# receiver.net
KiCad netlist of a schematic drawn in EAGLE
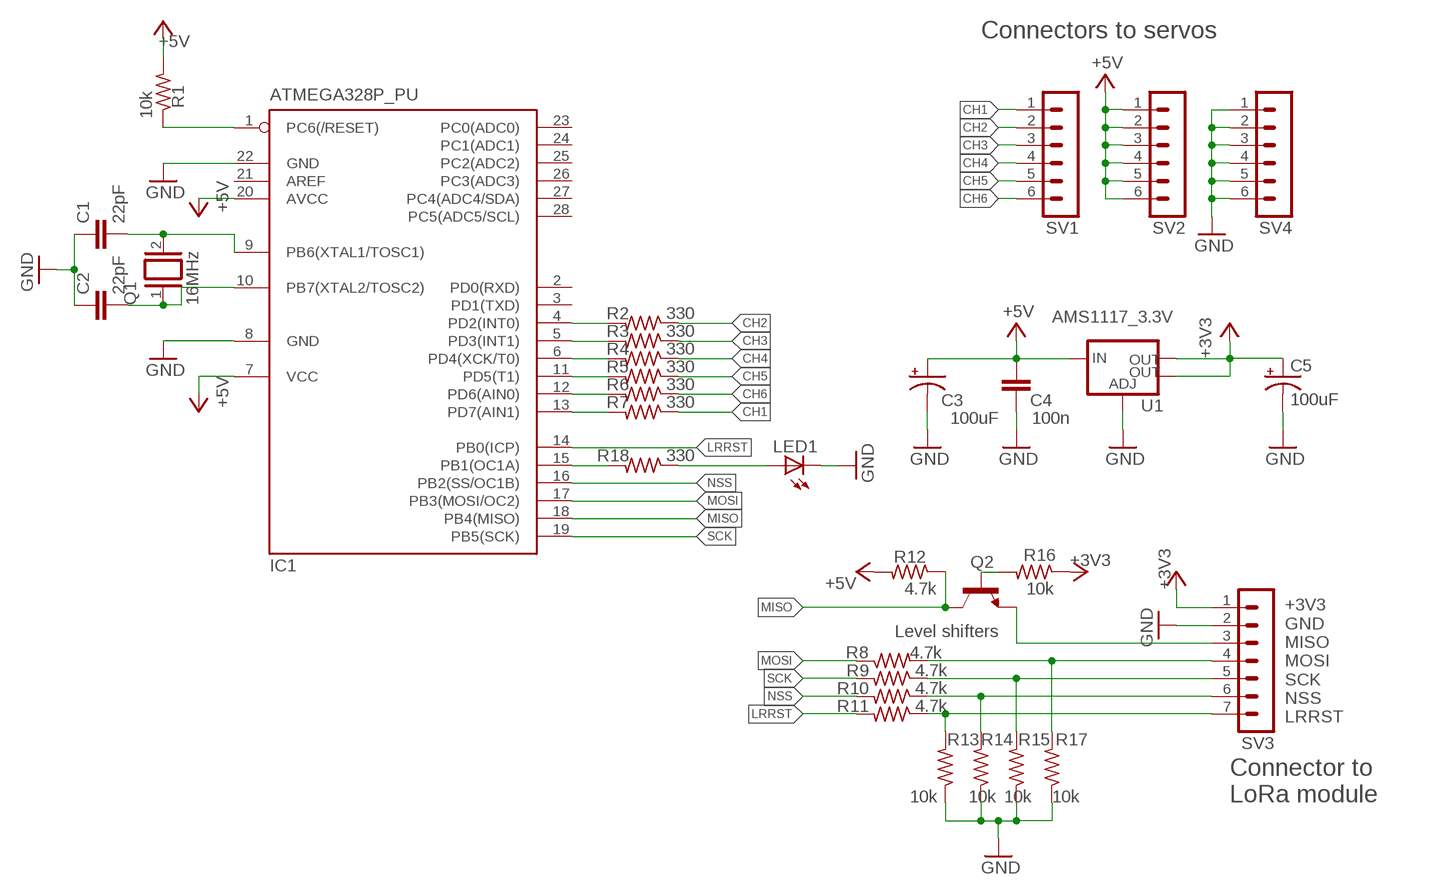
[diagram p0: schematic, sheet 1]

(export (version "E")
  (design (tool "Eeschema 10.0.6"))
  (components
    (comp (ref "C1")
      (value "22pF")
      (footprint "eagle-import:C025-025X050")
      (libsource (lib "eagle-import") (part "C-EU025-025X050"))
    )
    (comp (ref "C2")
      (value "22pF")
      (footprint "eagle-import:C025-025X050")
      (libsource (lib "eagle-import") (part "C-EU025-025X050"))
    )
    (comp (ref "C3")
      (value "100uF")
      (footprint "eagle-import:E2,5-6E")
      (libsource (lib "eagle-import") (part "CPOL-USE2,5-6E"))
    )
    (comp (ref "C4")
      (value "100n")
      (footprint "eagle-import:C025-025X050")
      (libsource (lib "eagle-import") (part "C-EU025-025X050"))
    )
    (comp (ref "C5")
      (value "100uF")
      (footprint "eagle-import:E2,5-6E")
      (libsource (lib "eagle-import") (part "CPOL-USE2,5-6E"))
    )
    (comp (ref "IC1")
      (value "ATMEGA328P_PU")
      (footprint "eagle-import:DIL28-3")
      (libsource (lib "eagle-import") (part "MEGA8-P"))
    )
    (comp (ref "LED1")
      (value "LED3MM")
      (footprint "eagle-import:LED3MM")
      (libsource (lib "eagle-import") (part "LED3MM"))
    )
    (comp (ref "Q1")
      (value "16MHz")
      (footprint "eagle-import:QS")
      (libsource (lib "eagle-import") (part "XTAL/S"))
    )
    (comp (ref "Q2")
      (value "BC817-16SMD")
      (footprint "eagle-import:SOT23-BEC")
      (libsource (lib "eagle-import") (part "BC817SMD-16"))
    )
    (comp (ref "R1")
      (value "10k")
      (footprint "eagle-import:R0805")
      (libsource (lib "eagle-import") (part "R-US_R0805"))
    )
    (comp (ref "R2")
      (value "330")
      (footprint "eagle-import:R0805")
      (libsource (lib "eagle-import") (part "R-US_R0805"))
    )
    (comp (ref "R3")
      (value "330")
      (footprint "eagle-import:R0805")
      (libsource (lib "eagle-import") (part "R-US_R0805"))
    )
    (comp (ref "R4")
      (value "330")
      (footprint "eagle-import:R0805")
      (libsource (lib "eagle-import") (part "R-US_R0805"))
    )
    (comp (ref "R5")
      (value "330")
      (footprint "eagle-import:R0805")
      (libsource (lib "eagle-import") (part "R-US_R0805"))
    )
    (comp (ref "R6")
      (value "330")
      (footprint "eagle-import:R0805")
      (libsource (lib "eagle-import") (part "R-US_R0805"))
    )
    (comp (ref "R7")
      (value "330")
      (footprint "eagle-import:R0805")
      (libsource (lib "eagle-import") (part "R-US_R0805"))
    )
    (comp (ref "R8")
      (value "4.7k")
      (footprint "eagle-import:R0805")
      (libsource (lib "eagle-import") (part "R-US_R0805"))
    )
    (comp (ref "R9")
      (value "4.7k")
      (footprint "eagle-import:R0805")
      (libsource (lib "eagle-import") (part "R-US_R0805"))
    )
    (comp (ref "R10")
      (value "4.7k")
      (footprint "eagle-import:R0805")
      (libsource (lib "eagle-import") (part "R-US_R0805"))
    )
    (comp (ref "R11")
      (value "4.7k")
      (footprint "eagle-import:R0805")
      (libsource (lib "eagle-import") (part "R-US_R0805"))
    )
    (comp (ref "R12")
      (value "4.7k")
      (footprint "eagle-import:R0805")
      (libsource (lib "eagle-import") (part "R-US_R0805"))
    )
    (comp (ref "R13")
      (value "10k")
      (footprint "eagle-import:R0805")
      (libsource (lib "eagle-import") (part "R-US_R0805"))
    )
    (comp (ref "R14")
      (value "10k")
      (footprint "eagle-import:R0805")
      (libsource (lib "eagle-import") (part "R-US_R0805"))
    )
    (comp (ref "R15")
      (value "10k")
      (footprint "eagle-import:R0805")
      (libsource (lib "eagle-import") (part "R-US_R0805"))
    )
    (comp (ref "R16")
      (value "10k")
      (footprint "eagle-import:R0805")
      (libsource (lib "eagle-import") (part "R-US_R0805"))
    )
    (comp (ref "R17")
      (value "10k")
      (footprint "eagle-import:R0805")
      (libsource (lib "eagle-import") (part "R-US_R0805"))
    )
    (comp (ref "R18")
      (value "330")
      (footprint "eagle-import:R0805")
      (libsource (lib "eagle-import") (part "R-US_R0805"))
    )
    (comp (ref "SV1")
      (value "MA06-1")
      (footprint "eagle-import:MA06-1")
      (libsource (lib "eagle-import") (part "MA06-1"))
    )
    (comp (ref "SV2")
      (value "MA06-1")
      (footprint "eagle-import:MA06-1")
      (libsource (lib "eagle-import") (part "MA06-1"))
    )
    (comp (ref "SV3")
      (value "MA07-1")
      (footprint "eagle-import:MA07-1")
      (libsource (lib "eagle-import") (part "MA07-1"))
    )
    (comp (ref "SV4")
      (value "MA06-1")
      (footprint "eagle-import:MA06-1")
      (libsource (lib "eagle-import") (part "MA06-1"))
    )
    (comp (ref "U1")
      (value "AMS1117_3.3V")
      (footprint "eagle-import:SOT223")
      (libsource (lib "eagle-import") (part "V_REG_LM1117SOT223"))
    )
  )
  (nets
    (net (code "1") (name "+3V3") (class "Default")
      (node (ref "C5") (pin "+") (pinfunction "+_+") (pintype "passive"))
      (node (ref "R16") (pin "1") (pinfunction "1_1") (pintype "passive"))
      (node (ref "SV3") (pin "1") (pinfunction "1_1") (pintype "passive"))
      (node (ref "U1") (pin "2") (pinfunction "OUT_2") (pintype "output"))
      (node (ref "U1") (pin "4") (pinfunction "OUT_4") (pintype "output"))
    )
    (net (code "2") (name "+5V") (class "Default")
      (node (ref "C3") (pin "+") (pinfunction "+_+") (pintype "passive"))
      (node (ref "C4") (pin "2") (pinfunction "2_2") (pintype "passive"))
      (node (ref "IC1") (pin "20") (pinfunction "AVCC_20") (pintype "power_in"))
      (node (ref "IC1") (pin "7") (pinfunction "VCC_7") (pintype "power_in"))
      (node (ref "R1") (pin "2") (pinfunction "2_2") (pintype "passive"))
      (node (ref "R12") (pin "2") (pinfunction "2_2") (pintype "passive"))
      (node (ref "SV2") (pin "1") (pinfunction "1_1") (pintype "passive"))
      (node (ref "SV2") (pin "2") (pinfunction "2_2") (pintype "passive"))
      (node (ref "SV2") (pin "3") (pinfunction "3_3") (pintype "passive"))
      (node (ref "SV2") (pin "4") (pinfunction "4_4") (pintype "passive"))
      (node (ref "SV2") (pin "5") (pinfunction "5_5") (pintype "passive"))
      (node (ref "SV2") (pin "6") (pinfunction "6_6") (pintype "passive"))
      (node (ref "U1") (pin "3") (pinfunction "IN_3") (pintype "input"))
    )
    (net (code "3") (name "CH1") (class "Default")
      (node (ref "R7") (pin "1") (pinfunction "1_1") (pintype "passive"))
      (node (ref "SV1") (pin "1") (pinfunction "1_1") (pintype "passive"))
    )
    (net (code "4") (name "CH2") (class "Default")
      (node (ref "R2") (pin "1") (pinfunction "1_1") (pintype "passive"))
      (node (ref "SV1") (pin "2") (pinfunction "2_2") (pintype "passive"))
    )
    (net (code "5") (name "CH3") (class "Default")
      (node (ref "R3") (pin "1") (pinfunction "1_1") (pintype "passive"))
      (node (ref "SV1") (pin "3") (pinfunction "3_3") (pintype "passive"))
    )
    (net (code "6") (name "CH4") (class "Default")
      (node (ref "R4") (pin "1") (pinfunction "1_1") (pintype "passive"))
      (node (ref "SV1") (pin "4") (pinfunction "4_4") (pintype "passive"))
    )
    (net (code "7") (name "CH5") (class "Default")
      (node (ref "R5") (pin "1") (pinfunction "1_1") (pintype "passive"))
      (node (ref "SV1") (pin "5") (pinfunction "5_5") (pintype "passive"))
    )
    (net (code "8") (name "CH6") (class "Default")
      (node (ref "R6") (pin "1") (pinfunction "1_1") (pintype "passive"))
      (node (ref "SV1") (pin "6") (pinfunction "6_6") (pintype "passive"))
    )
    (net (code "9") (name "GND") (class "Default")
      (node (ref "C1") (pin "1") (pinfunction "1_1") (pintype "passive"))
      (node (ref "C2") (pin "1") (pinfunction "1_1") (pintype "passive"))
      (node (ref "C3") (pin "-") (pinfunction "-_-") (pintype "passive"))
      (node (ref "C4") (pin "1") (pinfunction "1_1") (pintype "passive"))
      (node (ref "C5") (pin "-") (pinfunction "-_-") (pintype "passive"))
      (node (ref "IC1") (pin "22") (pinfunction "GND_22") (pintype "power_in"))
      (node (ref "IC1") (pin "8") (pinfunction "GND_8") (pintype "power_in"))
      (node (ref "LED1") (pin "K") (pinfunction "C_K") (pintype "passive"))
      (node (ref "R13") (pin "1") (pinfunction "1_1") (pintype "passive"))
      (node (ref "R14") (pin "1") (pinfunction "1_1") (pintype "passive"))
      (node (ref "R15") (pin "1") (pinfunction "1_1") (pintype "passive"))
      (node (ref "R17") (pin "1") (pinfunction "1_1") (pintype "passive"))
      (node (ref "SV3") (pin "2") (pinfunction "2_2") (pintype "passive"))
      (node (ref "SV4") (pin "1") (pinfunction "1_1") (pintype "passive"))
      (node (ref "SV4") (pin "2") (pinfunction "2_2") (pintype "passive"))
      (node (ref "SV4") (pin "3") (pinfunction "3_3") (pintype "passive"))
      (node (ref "SV4") (pin "4") (pinfunction "4_4") (pintype "passive"))
      (node (ref "SV4") (pin "5") (pinfunction "5_5") (pintype "passive"))
      (node (ref "SV4") (pin "6") (pinfunction "6_6") (pintype "passive"))
      (node (ref "U1") (pin "1") (pinfunction "ADJ_1") (pintype "input"))
    )
    (net (code "10") (name "LRRST") (class "Default")
      (node (ref "IC1") (pin "14") (pinfunction "PB0(ICP)_14") (pintype "bidirectional"))
      (node (ref "R11") (pin "2") (pinfunction "2_2") (pintype "passive"))
    )
    (net (code "11") (name "MISO") (class "Default")
      (node (ref "IC1") (pin "18") (pinfunction "PB4(MISO)_18") (pintype "bidirectional"))
      (node (ref "Q2") (pin "C") (pinfunction "C_C") (pintype "passive"))
      (node (ref "R12") (pin "1") (pinfunction "1_1") (pintype "passive"))
    )
    (net (code "12") (name "MOSI") (class "Default")
      (node (ref "IC1") (pin "17") (pinfunction "PB3(MOSI/OC2)_17") (pintype "bidirectional"))
      (node (ref "R8") (pin "1") (pinfunction "1_1") (pintype "passive"))
    )
    (net (code "13") (name "NSS") (class "Default")
      (node (ref "IC1") (pin "16") (pinfunction "PB2(SS/OC1B)_16") (pintype "bidirectional"))
      (node (ref "R10") (pin "2") (pinfunction "2_2") (pintype "passive"))
    )
    (net (code "14") (name "Net-(IC1-PB1(OC1A))") (class "Default")
      (node (ref "IC1") (pin "15") (pinfunction "PB1(OC1A)_15") (pintype "bidirectional"))
      (node (ref "R18") (pin "2") (pinfunction "2_2") (pintype "passive"))
    )
    (net (code "15") (name "Net-(IC1-PB6(XTAL1{slash}TOSC1))") (class "Default")
      (node (ref "C1") (pin "2") (pinfunction "2_2") (pintype "passive"))
      (node (ref "IC1") (pin "9") (pinfunction "PB6(XTAL1/TOSC1)_9") (pintype "bidirectional"))
      (node (ref "Q1") (pin "2") (pinfunction "2_2") (pintype "passive"))
    )
    (net (code "16") (name "Net-(IC1-PB7(XTAL2{slash}TOSC2))") (class "Default")
      (node (ref "C2") (pin "2") (pinfunction "2_2") (pintype "passive"))
      (node (ref "IC1") (pin "10") (pinfunction "PB7(XTAL2/TOSC2)_10") (pintype "bidirectional"))
      (node (ref "Q1") (pin "1") (pinfunction "1_1") (pintype "passive"))
    )
    (net (code "17") (name "Net-(IC1-PC6({slash}RESET))") (class "Default")
      (node (ref "IC1") (pin "1") (pinfunction "PC6(/RESET)_1") (pintype "bidirectional"))
      (node (ref "R1") (pin "1") (pinfunction "1_1") (pintype "passive"))
    )
    (net (code "18") (name "Net-(IC1-PD2(INT0))") (class "Default")
      (node (ref "IC1") (pin "4") (pinfunction "PD2(INT0)_4") (pintype "bidirectional"))
      (node (ref "R2") (pin "2") (pinfunction "2_2") (pintype "passive"))
    )
    (net (code "19") (name "Net-(IC1-PD3(INT1))") (class "Default")
      (node (ref "IC1") (pin "5") (pinfunction "PD3(INT1)_5") (pintype "bidirectional"))
      (node (ref "R3") (pin "2") (pinfunction "2_2") (pintype "passive"))
    )
    (net (code "20") (name "Net-(IC1-PD4(XCK{slash}T0))") (class "Default")
      (node (ref "IC1") (pin "6") (pinfunction "PD4(XCK/T0)_6") (pintype "bidirectional"))
      (node (ref "R4") (pin "2") (pinfunction "2_2") (pintype "passive"))
    )
    (net (code "21") (name "Net-(IC1-PD5(T1))") (class "Default")
      (node (ref "IC1") (pin "11") (pinfunction "PD5(T1)_11") (pintype "bidirectional"))
      (node (ref "R5") (pin "2") (pinfunction "2_2") (pintype "passive"))
    )
    (net (code "22") (name "Net-(IC1-PD6(AIN0))") (class "Default")
      (node (ref "IC1") (pin "12") (pinfunction "PD6(AIN0)_12") (pintype "bidirectional"))
      (node (ref "R6") (pin "2") (pinfunction "2_2") (pintype "passive"))
    )
    (net (code "23") (name "Net-(IC1-PD7(AIN1))") (class "Default")
      (node (ref "IC1") (pin "13") (pinfunction "PD7(AIN1)_13") (pintype "bidirectional"))
      (node (ref "R7") (pin "2") (pinfunction "2_2") (pintype "passive"))
    )
    (net (code "24") (name "Net-(LED1-PadA)") (class "Default")
      (node (ref "LED1") (pin "A") (pinfunction "A_A") (pintype "passive"))
      (node (ref "R18") (pin "1") (pinfunction "1_1") (pintype "passive"))
    )
    (net (code "25") (name "Net-(Q2-PadB)") (class "Default")
      (node (ref "Q2") (pin "B") (pinfunction "B_B") (pintype "passive"))
      (node (ref "R16") (pin "2") (pinfunction "2_2") (pintype "passive"))
    )
    (net (code "26") (name "Net-(Q2-PadE)") (class "Default")
      (node (ref "Q2") (pin "E") (pinfunction "E_E") (pintype "passive"))
      (node (ref "SV3") (pin "3") (pinfunction "3_3") (pintype "passive"))
    )
    (net (code "27") (name "Net-(R10-Pad1)") (class "Default")
      (node (ref "R10") (pin "1") (pinfunction "1_1") (pintype "passive"))
      (node (ref "R14") (pin "2") (pinfunction "2_2") (pintype "passive"))
      (node (ref "SV3") (pin "6") (pinfunction "6_6") (pintype "passive"))
    )
    (net (code "28") (name "Net-(R11-Pad1)") (class "Default")
      (node (ref "R11") (pin "1") (pinfunction "1_1") (pintype "passive"))
      (node (ref "R13") (pin "2") (pinfunction "2_2") (pintype "passive"))
      (node (ref "SV3") (pin "7") (pinfunction "7_7") (pintype "passive"))
    )
    (net (code "29") (name "Net-(R15-Pad2)") (class "Default")
      (node (ref "R15") (pin "2") (pinfunction "2_2") (pintype "passive"))
      (node (ref "R9") (pin "1") (pinfunction "1_1") (pintype "passive"))
      (node (ref "SV3") (pin "5") (pinfunction "5_5") (pintype "passive"))
    )
    (net (code "30") (name "Net-(R17-Pad2)") (class "Default")
      (node (ref "R17") (pin "2") (pinfunction "2_2") (pintype "passive"))
      (node (ref "R8") (pin "2") (pinfunction "2_2") (pintype "passive"))
      (node (ref "SV3") (pin "4") (pinfunction "4_4") (pintype "passive"))
    )
    (net (code "31") (name "SCK") (class "Default")
      (node (ref "IC1") (pin "19") (pinfunction "PB5(SCK)_19") (pintype "bidirectional"))
      (node (ref "R9") (pin "2") (pinfunction "2_2") (pintype "passive"))
    )
    (net (code "32") (name "unconnected-(IC1-AREF-Pad21)") (class "Default")
      (node (ref "IC1") (pin "21") (pinfunction "AREF_21") (pintype "passive"))
    )
    (net (code "33") (name "unconnected-(IC1-PC0(ADC0)-Pad23)") (class "Default")
      (node (ref "IC1") (pin "23") (pinfunction "PC0(ADC0)_23") (pintype "bidirectional"))
    )
    (net (code "34") (name "unconnected-(IC1-PC1(ADC1)-Pad24)") (class "Default")
      (node (ref "IC1") (pin "24") (pinfunction "PC1(ADC1)_24") (pintype "bidirectional"))
    )
    (net (code "35") (name "unconnected-(IC1-PC2(ADC2)-Pad25)") (class "Default")
      (node (ref "IC1") (pin "25") (pinfunction "PC2(ADC2)_25") (pintype "bidirectional"))
    )
    (net (code "36") (name "unconnected-(IC1-PC3(ADC3)-Pad26)") (class "Default")
      (node (ref "IC1") (pin "26") (pinfunction "PC3(ADC3)_26") (pintype "bidirectional"))
    )
    (net (code "37") (name "unconnected-(IC1-PC4(ADC4{slash}SDA)-Pad27)") (class "Default")
      (node (ref "IC1") (pin "27") (pinfunction "PC4(ADC4/SDA)_27") (pintype "bidirectional"))
    )
    (net (code "38") (name "unconnected-(IC1-PC5(ADC5{slash}SCL)-Pad28)") (class "Default")
      (node (ref "IC1") (pin "28") (pinfunction "PC5(ADC5/SCL)_28") (pintype "bidirectional"))
    )
    (net (code "39") (name "unconnected-(IC1-PD0(RXD)-Pad2)") (class "Default")
      (node (ref "IC1") (pin "2") (pinfunction "PD0(RXD)_2") (pintype "bidirectional"))
    )
    (net (code "40") (name "unconnected-(IC1-PD1(TXD)-Pad3)") (class "Default")
      (node (ref "IC1") (pin "3") (pinfunction "PD1(TXD)_3") (pintype "bidirectional"))
    )
  )
)
